# HeadphoneMixer.net
KiCad netlist of a schematic drawn in EAGLE
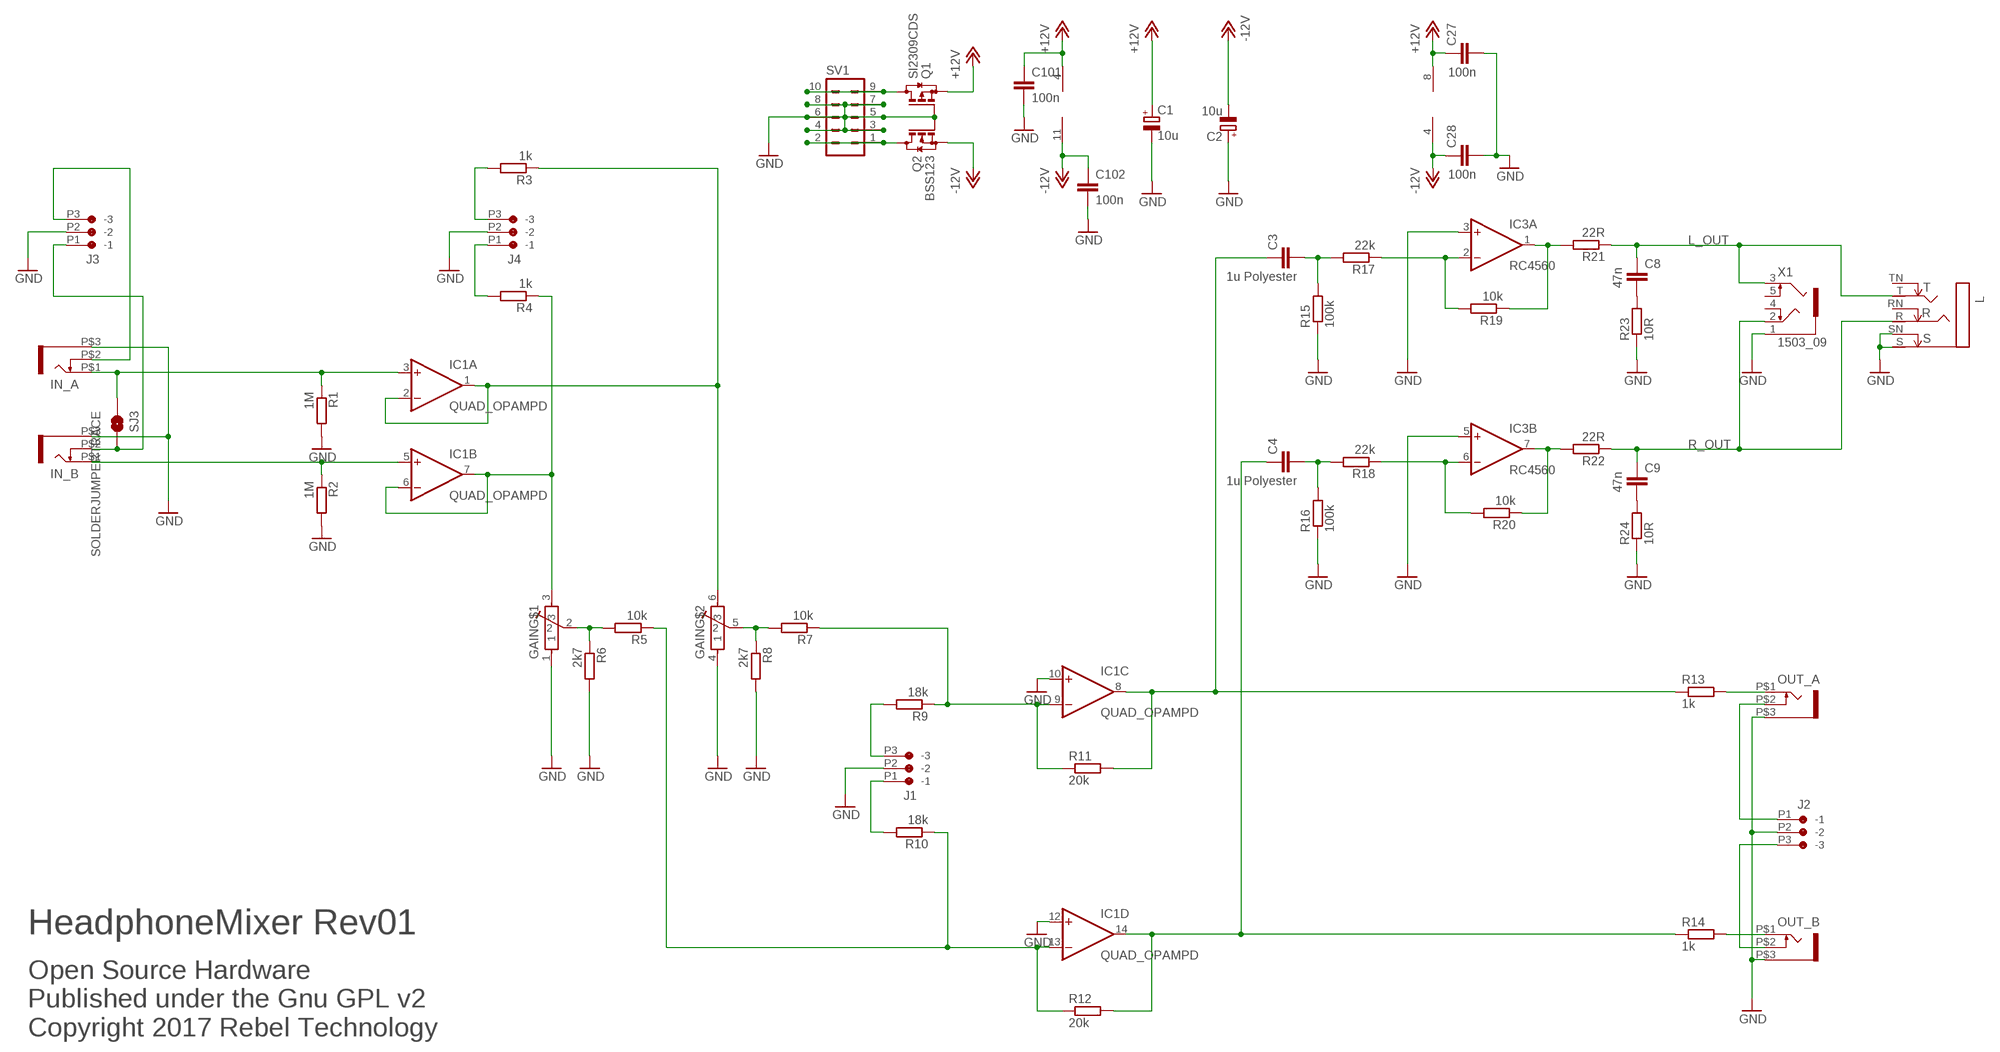
[diagram p0: schematic, sheet 1]

(export (version "E")
  (design (tool "Eeschema 10.0.6"))
  (components
    (comp (ref "C1")
      (value "10u")
      (footprint "eagle-import:153CLV-0505")
      (libsource (lib "eagle-import") (part "CPOL-EU153CLV-0505"))
    )
    (comp (ref "C2")
      (value "10u")
      (footprint "eagle-import:153CLV-0505")
      (libsource (lib "eagle-import") (part "CPOL-EU153CLV-0505"))
    )
    (comp (ref "C3")
      (value "1u Polyester")
      (footprint "eagle-import:C1210")
      (libsource (lib "eagle-import") (part "C-EUC1210"))
    )
    (comp (ref "C4")
      (value "1u Polyester")
      (footprint "eagle-import:C1210")
      (libsource (lib "eagle-import") (part "C-EUC1210"))
    )
    (comp (ref "C8")
      (value "47n")
      (footprint "eagle-import:C0603")
      (libsource (lib "eagle-import") (part "C-EUC0603"))
    )
    (comp (ref "C9")
      (value "47n")
      (footprint "eagle-import:C0603")
      (libsource (lib "eagle-import") (part "C-EUC0603"))
    )
    (comp (ref "C27")
      (value "100n")
      (footprint "eagle-import:C0603")
      (libsource (lib "eagle-import") (part "C-EUC0603"))
    )
    (comp (ref "C28")
      (value "100n")
      (footprint "eagle-import:C0603")
      (libsource (lib "eagle-import") (part "C-EUC0603"))
    )
    (comp (ref "C101")
      (value "100n")
      (footprint "eagle-import:C0603")
      (libsource (lib "eagle-import") (part "C-EUC0603"))
    )
    (comp (ref "C102")
      (value "100n")
      (footprint "eagle-import:C0603")
      (libsource (lib "eagle-import") (part "C-EUC0603"))
    )
    (comp (ref "GAIN")
      (value "POT-BOURNS-PTD902")
      (footprint "eagle-import:POT-BOURNS-PTD902")
      (libsource (lib "eagle-import") (part "POT-BOURNS-PTD902"))
    )
    (comp (ref "IC1")
      (value "QUAD_OPAMPD")
      (footprint "eagle-import:SO14")
      (libsource (lib "eagle-import") (part "QUAD_OPAMPD"))
    )
    (comp (ref "IC3")
      (value "RC4560")
      (footprint "eagle-import:SO08")
      (libsource (lib "eagle-import") (part "NE5532D"))
    )
    (comp (ref "IN_A")
      (value "JACK-UJ-3502-R")
      (footprint "eagle-import:UJ-3502-R")
      (libsource (lib "eagle-import") (part "JACK-UJ-3502-R"))
    )
    (comp (ref "IN_B")
      (value "JACK-UJ-3502-R")
      (footprint "eagle-import:UJ-3502-R")
      (libsource (lib "eagle-import") (part "JACK-UJ-3502-R"))
    )
    (comp (ref "J1")
      (value "CON-JST_PH_3W")
      (footprint "eagle-import:CON-JST_PH_3W")
      (libsource (lib "eagle-import") (part "CON-JST_PH_3W"))
    )
    (comp (ref "J2")
      (value "CON-JST_PH_3W")
      (footprint "eagle-import:CON-JST_PH_3W")
      (libsource (lib "eagle-import") (part "CON-JST_PH_3W"))
    )
    (comp (ref "J3")
      (value "CON-JST_PH_3W")
      (footprint "eagle-import:CON-JST_PH_3W")
      (libsource (lib "eagle-import") (part "CON-JST_PH_3W"))
    )
    (comp (ref "J4")
      (value "CON-JST_PH_3W")
      (footprint "eagle-import:CON-JST_PH_3W")
      (libsource (lib "eagle-import") (part "CON-JST_PH_3W"))
    )
    (comp (ref "L")
      (value "NEUTRIK_NMJ6HCD2")
      (footprint "eagle-import:NMJ6HCD2")
      (libsource (lib "eagle-import") (part "NEUTRIK_NMJ6HCD2"))
    )
    (comp (ref "OUT_A")
      (value "JACK-UJ-3502-R")
      (footprint "eagle-import:UJ-3502-R")
      (libsource (lib "eagle-import") (part "JACK-UJ-3502-R"))
    )
    (comp (ref "OUT_B")
      (value "JACK-UJ-3502-R")
      (footprint "eagle-import:UJ-3502-R")
      (libsource (lib "eagle-import") (part "JACK-UJ-3502-R"))
    )
    (comp (ref "Q1")
      (value "SI2309CDS")
      (footprint "eagle-import:SOT23")
      (libsource (lib "eagle-import") (part "BSS84"))
    )
    (comp (ref "Q2")
      (value "BSS123")
      (footprint "eagle-import:SOT23")
      (libsource (lib "eagle-import") (part "BSS123"))
    )
    (comp (ref "R1")
      (value "1M")
      (footprint "eagle-import:0603")
      (libsource (lib "eagle-import") (part "R-EU_0603"))
    )
    (comp (ref "R2")
      (value "1M")
      (footprint "eagle-import:0603")
      (libsource (lib "eagle-import") (part "R-EU_0603"))
    )
    (comp (ref "R3")
      (value "1k")
      (footprint "eagle-import:0603")
      (libsource (lib "eagle-import") (part "R-EU_0603"))
    )
    (comp (ref "R4")
      (value "1k")
      (footprint "eagle-import:0603")
      (libsource (lib "eagle-import") (part "R-EU_0603"))
    )
    (comp (ref "R5")
      (value "10k")
      (footprint "eagle-import:0603")
      (libsource (lib "eagle-import") (part "R-EU_0603"))
    )
    (comp (ref "R6")
      (value "2k7")
      (footprint "eagle-import:0603")
      (libsource (lib "eagle-import") (part "R-EU_0603"))
    )
    (comp (ref "R7")
      (value "10k")
      (footprint "eagle-import:0603")
      (libsource (lib "eagle-import") (part "R-EU_0603"))
    )
    (comp (ref "R8")
      (value "2k7")
      (footprint "eagle-import:0603")
      (libsource (lib "eagle-import") (part "R-EU_0603"))
    )
    (comp (ref "R9")
      (value "18k")
      (footprint "eagle-import:0603")
      (libsource (lib "eagle-import") (part "R-EU_0603"))
    )
    (comp (ref "R10")
      (value "18k")
      (footprint "eagle-import:0603")
      (libsource (lib "eagle-import") (part "R-EU_0603"))
    )
    (comp (ref "R11")
      (value "20k")
      (footprint "eagle-import:0603")
      (libsource (lib "eagle-import") (part "R-EU_0603"))
    )
    (comp (ref "R12")
      (value "20k")
      (footprint "eagle-import:0603")
      (libsource (lib "eagle-import") (part "R-EU_0603"))
    )
    (comp (ref "R13")
      (value "1k")
      (footprint "eagle-import:0603")
      (libsource (lib "eagle-import") (part "R-EU_0603"))
    )
    (comp (ref "R14")
      (value "1k")
      (footprint "eagle-import:0603")
      (libsource (lib "eagle-import") (part "R-EU_0603"))
    )
    (comp (ref "R15")
      (value "100k")
      (footprint "eagle-import:0603")
      (libsource (lib "eagle-import") (part "R-EU_0603"))
    )
    (comp (ref "R16")
      (value "100k")
      (footprint "eagle-import:0603")
      (libsource (lib "eagle-import") (part "R-EU_0603"))
    )
    (comp (ref "R17")
      (value "22k")
      (footprint "eagle-import:0603")
      (libsource (lib "eagle-import") (part "R-EU_0603"))
    )
    (comp (ref "R18")
      (value "22k")
      (footprint "eagle-import:0603")
      (libsource (lib "eagle-import") (part "R-EU_0603"))
    )
    (comp (ref "R19")
      (value "10k")
      (footprint "eagle-import:0603")
      (libsource (lib "eagle-import") (part "R-EU_0603"))
    )
    (comp (ref "R20")
      (value "10k")
      (footprint "eagle-import:0603")
      (libsource (lib "eagle-import") (part "R-EU_0603"))
    )
    (comp (ref "R21")
      (value "22R")
      (footprint "eagle-import:0603")
      (libsource (lib "eagle-import") (part "R-EU_0603"))
    )
    (comp (ref "R22")
      (value "22R")
      (footprint "eagle-import:0603")
      (libsource (lib "eagle-import") (part "R-EU_0603"))
    )
    (comp (ref "R23")
      (value "10R")
      (footprint "eagle-import:0603")
      (libsource (lib "eagle-import") (part "R-EU_0603"))
    )
    (comp (ref "R24")
      (value "10R")
      (footprint "eagle-import:0603")
      (libsource (lib "eagle-import") (part "R-EU_0603"))
    )
    (comp (ref "SJ3")
      (value "SOLDERJUMPERTRACE")
      (footprint "eagle-import:SJ_2S-TRACE")
      (libsource (lib "eagle-import") (part "SOLDERJUMPERTRACE"))
    )
    (comp (ref "SV1")
      (value "MA05-2")
      (footprint "eagle-import:MA05-2")
      (libsource (lib "eagle-import") (part "MA05-2"))
    )
    (comp (ref "X1")
      (value "1503_09")
      (footprint "eagle-import:1503_09")
      (libsource (lib "eagle-import") (part "1503_09"))
    )
  )
  (nets
    (net (code "1") (name "+12V") (class "Default")
      (node (ref "C1") (pin "+") (pinfunction "+_+") (pintype "passive"))
      (node (ref "C101") (pin "1") (pinfunction "1_1") (pintype "passive"))
      (node (ref "C27") (pin "1") (pinfunction "1_1") (pintype "passive"))
      (node (ref "IC1") (pin "4") (pinfunction "V+_4") (pintype "power_in"))
      (node (ref "IC3") (pin "8") (pinfunction "V+_8") (pintype "power_in"))
      (node (ref "Q1") (pin "2") (pinfunction "S_2") (pintype "passive"))
    )
    (net (code "2") (name "-12V") (class "Default")
      (node (ref "C102") (pin "1") (pinfunction "1_1") (pintype "passive"))
      (node (ref "C2") (pin "-") (pinfunction "-_-") (pintype "passive"))
      (node (ref "C28") (pin "1") (pinfunction "1_1") (pintype "passive"))
      (node (ref "IC1") (pin "11") (pinfunction "V-_11") (pintype "power_in"))
      (node (ref "IC3") (pin "4") (pinfunction "V-_4") (pintype "power_in"))
      (node (ref "Q2") (pin "2") (pinfunction "S_2") (pintype "passive"))
    )
    (net (code "3") (name "/L_OUT") (class "Default")
      (node (ref "C8") (pin "1") (pinfunction "1_1") (pintype "passive"))
      (node (ref "L") (pin "T") (pinfunction "T_T") (pintype "passive"))
      (node (ref "R21") (pin "1") (pinfunction "1_1") (pintype "passive"))
      (node (ref "X1") (pin "3") (pinfunction "3_3") (pintype "passive"))
    )
    (net (code "4") (name "/R_OUT") (class "Default")
      (node (ref "C9") (pin "1") (pinfunction "1_1") (pintype "passive"))
      (node (ref "L") (pin "R") (pinfunction "R_R") (pintype "passive"))
      (node (ref "R22") (pin "1") (pinfunction "1_1") (pintype "passive"))
      (node (ref "X1") (pin "2") (pinfunction "2_2") (pintype "passive"))
    )
    (net (code "5") (name "GND") (class "Default")
      (node (ref "C1") (pin "-") (pinfunction "-_-") (pintype "passive"))
      (node (ref "C101") (pin "2") (pinfunction "2_2") (pintype "passive"))
      (node (ref "C102") (pin "2") (pinfunction "2_2") (pintype "passive"))
      (node (ref "C2") (pin "+") (pinfunction "+_+") (pintype "passive"))
      (node (ref "C27") (pin "2") (pinfunction "2_2") (pintype "passive"))
      (node (ref "C28") (pin "2") (pinfunction "2_2") (pintype "passive"))
      (node (ref "GAIN") (pin "1") (pinfunction "1_1") (pintype "bidirectional"))
      (node (ref "GAIN") (pin "4") (pinfunction "1_4") (pintype "bidirectional"))
      (node (ref "IC1") (pin "10") (pinfunction "+IN_10") (pintype "input"))
      (node (ref "IC1") (pin "12") (pinfunction "+IN_12") (pintype "input"))
      (node (ref "IC3") (pin "3") (pinfunction "+IN_3") (pintype "input"))
      (node (ref "IC3") (pin "5") (pinfunction "+IN_5") (pintype "input"))
      (node (ref "IN_A") (pin "P$3") (pinfunction "SLEEVE_P$3") (pintype "passive"))
      (node (ref "IN_B") (pin "P$3") (pinfunction "SLEEVE_P$3") (pintype "passive"))
      (node (ref "J1") (pin "P2") (pinfunction "-2_P2") (pintype "bidirectional"))
      (node (ref "J2") (pin "P2") (pinfunction "-2_P2") (pintype "bidirectional"))
      (node (ref "J3") (pin "P2") (pinfunction "-2_P2") (pintype "bidirectional"))
      (node (ref "J4") (pin "P2") (pinfunction "-2_P2") (pintype "bidirectional"))
      (node (ref "L") (pin "S") (pinfunction "S_S") (pintype "passive"))
      (node (ref "L") (pin "SN") (pinfunction "SN_SN") (pintype "passive"))
      (node (ref "OUT_A") (pin "P$3") (pinfunction "SLEEVE_P$3") (pintype "passive"))
      (node (ref "OUT_B") (pin "P$3") (pinfunction "SLEEVE_P$3") (pintype "passive"))
      (node (ref "Q1") (pin "1") (pinfunction "G_1") (pintype "passive"))
      (node (ref "Q2") (pin "1") (pinfunction "G_1") (pintype "passive"))
      (node (ref "R1") (pin "2") (pinfunction "2_2") (pintype "passive"))
      (node (ref "R15") (pin "1") (pinfunction "1_1") (pintype "passive"))
      (node (ref "R16") (pin "1") (pinfunction "1_1") (pintype "passive"))
      (node (ref "R2") (pin "2") (pinfunction "2_2") (pintype "passive"))
      (node (ref "R23") (pin "1") (pinfunction "1_1") (pintype "passive"))
      (node (ref "R24") (pin "1") (pinfunction "1_1") (pintype "passive"))
      (node (ref "R6") (pin "2") (pinfunction "2_2") (pintype "passive"))
      (node (ref "R8") (pin "2") (pinfunction "2_2") (pintype "passive"))
      (node (ref "SV1") (pin "3") (pinfunction "3_3") (pintype "passive"))
      (node (ref "SV1") (pin "4") (pinfunction "4_4") (pintype "passive"))
      (node (ref "SV1") (pin "5") (pinfunction "5_5") (pintype "passive"))
      (node (ref "SV1") (pin "6") (pinfunction "6_6") (pintype "passive"))
      (node (ref "SV1") (pin "7") (pinfunction "7_7") (pintype "passive"))
      (node (ref "SV1") (pin "8") (pinfunction "8_8") (pintype "passive"))
      (node (ref "X1") (pin "1") (pinfunction "1_1") (pintype "passive"))
    )
    (net (code "6") (name "Net-(C3-Pad2)") (class "Default")
      (node (ref "C3") (pin "2") (pinfunction "2_2") (pintype "passive"))
      (node (ref "R15") (pin "2") (pinfunction "2_2") (pintype "passive"))
      (node (ref "R17") (pin "2") (pinfunction "2_2") (pintype "passive"))
    )
    (net (code "7") (name "Net-(C4-Pad2)") (class "Default")
      (node (ref "C4") (pin "2") (pinfunction "2_2") (pintype "passive"))
      (node (ref "R16") (pin "2") (pinfunction "2_2") (pintype "passive"))
      (node (ref "R18") (pin "2") (pinfunction "2_2") (pintype "passive"))
    )
    (net (code "8") (name "Net-(C8-Pad2)") (class "Default")
      (node (ref "C8") (pin "2") (pinfunction "2_2") (pintype "passive"))
      (node (ref "R23") (pin "2") (pinfunction "2_2") (pintype "passive"))
    )
    (net (code "9") (name "Net-(C9-Pad2)") (class "Default")
      (node (ref "C9") (pin "2") (pinfunction "2_2") (pintype "passive"))
      (node (ref "R24") (pin "2") (pinfunction "2_2") (pintype "passive"))
    )
    (net (code "10") (name "Net-(GAIN-Pad2)") (class "Default")
      (node (ref "GAIN") (pin "2") (pinfunction "2_2") (pintype "bidirectional"))
      (node (ref "R5") (pin "2") (pinfunction "2_2") (pintype "passive"))
      (node (ref "R6") (pin "1") (pinfunction "1_1") (pintype "passive"))
    )
    (net (code "11") (name "Net-(GAINB-2)") (class "Default")
      (node (ref "GAIN") (pin "5") (pinfunction "2_5") (pintype "bidirectional"))
      (node (ref "R7") (pin "2") (pinfunction "2_2") (pintype "passive"))
      (node (ref "R8") (pin "1") (pinfunction "1_1") (pintype "passive"))
    )
    (net (code "12") (name "Net-(GAINB-3)") (class "Default")
      (node (ref "GAIN") (pin "6") (pinfunction "3_6") (pintype "bidirectional"))
      (node (ref "IC1") (pin "1") (pinfunction "OUT_1") (pintype "output"))
      (node (ref "IC1") (pin "2") (pinfunction "-IN_2") (pintype "input"))
      (node (ref "R3") (pin "1") (pinfunction "1_1") (pintype "passive"))
    )
    (net (code "13") (name "Net-(IC1A-+IN)") (class "Default")
      (node (ref "IC1") (pin "3") (pinfunction "+IN_3") (pintype "input"))
      (node (ref "IN_A") (pin "P$1") (pinfunction "TIP_P$1") (pintype "passive"))
      (node (ref "R1") (pin "1") (pinfunction "1_1") (pintype "passive"))
      (node (ref "SJ3") (pin "1") (pinfunction "1_1") (pintype "passive"))
    )
    (net (code "14") (name "Net-(IC1B-+IN)") (class "Default")
      (node (ref "IC1") (pin "5") (pinfunction "+IN_5") (pintype "input"))
      (node (ref "IN_B") (pin "P$1") (pinfunction "TIP_P$1") (pintype "passive"))
      (node (ref "R2") (pin "1") (pinfunction "1_1") (pintype "passive"))
    )
    (net (code "15") (name "Net-(IC1B--IN)") (class "Default")
      (node (ref "GAIN") (pin "3") (pinfunction "3_3") (pintype "bidirectional"))
      (node (ref "IC1") (pin "6") (pinfunction "-IN_6") (pintype "input"))
      (node (ref "IC1") (pin "7") (pinfunction "OUT_7") (pintype "output"))
      (node (ref "R4") (pin "1") (pinfunction "1_1") (pintype "passive"))
    )
    (net (code "16") (name "Net-(IC1C--IN)") (class "Default")
      (node (ref "IC1") (pin "9") (pinfunction "-IN_9") (pintype "input"))
      (node (ref "R11") (pin "1") (pinfunction "1_1") (pintype "passive"))
      (node (ref "R7") (pin "1") (pinfunction "1_1") (pintype "passive"))
      (node (ref "R9") (pin "1") (pinfunction "1_1") (pintype "passive"))
    )
    (net (code "17") (name "Net-(IC1C-OUT)") (class "Default")
      (node (ref "C3") (pin "1") (pinfunction "1_1") (pintype "passive"))
      (node (ref "IC1") (pin "8") (pinfunction "OUT_8") (pintype "output"))
      (node (ref "R11") (pin "2") (pinfunction "2_2") (pintype "passive"))
      (node (ref "R13") (pin "1") (pinfunction "1_1") (pintype "passive"))
    )
    (net (code "18") (name "Net-(IC1D--IN)") (class "Default")
      (node (ref "IC1") (pin "13") (pinfunction "-IN_13") (pintype "input"))
      (node (ref "R10") (pin "1") (pinfunction "1_1") (pintype "passive"))
      (node (ref "R12") (pin "1") (pinfunction "1_1") (pintype "passive"))
      (node (ref "R5") (pin "1") (pinfunction "1_1") (pintype "passive"))
    )
    (net (code "19") (name "Net-(IC1D-OUT)") (class "Default")
      (node (ref "C4") (pin "1") (pinfunction "1_1") (pintype "passive"))
      (node (ref "IC1") (pin "14") (pinfunction "OUT_14") (pintype "output"))
      (node (ref "R12") (pin "2") (pinfunction "2_2") (pintype "passive"))
      (node (ref "R14") (pin "1") (pinfunction "1_1") (pintype "passive"))
    )
    (net (code "20") (name "Net-(IC3A--IN)") (class "Default")
      (node (ref "IC3") (pin "2") (pinfunction "-IN_2") (pintype "input"))
      (node (ref "R17") (pin "1") (pinfunction "1_1") (pintype "passive"))
      (node (ref "R19") (pin "2") (pinfunction "2_2") (pintype "passive"))
    )
    (net (code "21") (name "Net-(IC3A-OUT)") (class "Default")
      (node (ref "IC3") (pin "1") (pinfunction "OUT_1") (pintype "output"))
      (node (ref "R19") (pin "1") (pinfunction "1_1") (pintype "passive"))
      (node (ref "R21") (pin "2") (pinfunction "2_2") (pintype "passive"))
    )
    (net (code "22") (name "Net-(IC3B--IN)") (class "Default")
      (node (ref "IC3") (pin "6") (pinfunction "-IN_6") (pintype "input"))
      (node (ref "R18") (pin "1") (pinfunction "1_1") (pintype "passive"))
      (node (ref "R20") (pin "2") (pinfunction "2_2") (pintype "passive"))
    )
    (net (code "23") (name "Net-(IC3B-OUT)") (class "Default")
      (node (ref "IC3") (pin "7") (pinfunction "OUT_7") (pintype "output"))
      (node (ref "R20") (pin "1") (pinfunction "1_1") (pintype "passive"))
      (node (ref "R22") (pin "2") (pinfunction "2_2") (pintype "passive"))
    )
    (net (code "24") (name "Net-(IN_A-SW)") (class "Default")
      (node (ref "IN_A") (pin "P$2") (pinfunction "SW_P$2") (pintype "passive"))
      (node (ref "J3") (pin "P3") (pinfunction "-3_P3") (pintype "bidirectional"))
    )
    (net (code "25") (name "Net-(IN_B-SW)") (class "Default")
      (node (ref "IN_B") (pin "P$2") (pinfunction "SW_P$2") (pintype "passive"))
      (node (ref "J3") (pin "P1") (pinfunction "-1_P1") (pintype "bidirectional"))
      (node (ref "SJ3") (pin "2") (pinfunction "2_2") (pintype "passive"))
    )
    (net (code "26") (name "Net-(J1--1)") (class "Default")
      (node (ref "J1") (pin "P1") (pinfunction "-1_P1") (pintype "bidirectional"))
      (node (ref "R10") (pin "2") (pinfunction "2_2") (pintype "passive"))
    )
    (net (code "27") (name "Net-(J1--3)") (class "Default")
      (node (ref "J1") (pin "P3") (pinfunction "-3_P3") (pintype "bidirectional"))
      (node (ref "R9") (pin "2") (pinfunction "2_2") (pintype "passive"))
    )
    (net (code "28") (name "Net-(J2--1)") (class "Default")
      (node (ref "J2") (pin "P1") (pinfunction "-1_P1") (pintype "bidirectional"))
      (node (ref "OUT_A") (pin "P$2") (pinfunction "SW_P$2") (pintype "passive"))
    )
    (net (code "29") (name "Net-(J2--3)") (class "Default")
      (node (ref "J2") (pin "P3") (pinfunction "-3_P3") (pintype "bidirectional"))
      (node (ref "OUT_B") (pin "P$2") (pinfunction "SW_P$2") (pintype "passive"))
    )
    (net (code "30") (name "Net-(J4--1)") (class "Default")
      (node (ref "J4") (pin "P1") (pinfunction "-1_P1") (pintype "bidirectional"))
      (node (ref "R4") (pin "2") (pinfunction "2_2") (pintype "passive"))
    )
    (net (code "31") (name "Net-(J4--3)") (class "Default")
      (node (ref "J4") (pin "P3") (pinfunction "-3_P3") (pintype "bidirectional"))
      (node (ref "R3") (pin "2") (pinfunction "2_2") (pintype "passive"))
    )
    (net (code "32") (name "Net-(OUT_A-TIP)") (class "Default")
      (node (ref "OUT_A") (pin "P$1") (pinfunction "TIP_P$1") (pintype "passive"))
      (node (ref "R13") (pin "2") (pinfunction "2_2") (pintype "passive"))
    )
    (net (code "33") (name "Net-(OUT_B-TIP)") (class "Default")
      (node (ref "OUT_B") (pin "P$1") (pinfunction "TIP_P$1") (pintype "passive"))
      (node (ref "R14") (pin "2") (pinfunction "2_2") (pintype "passive"))
    )
    (net (code "34") (name "Net-(Q1-D)") (class "Default")
      (node (ref "Q1") (pin "3") (pinfunction "D_3") (pintype "passive"))
      (node (ref "SV1") (pin "10") (pinfunction "10_10") (pintype "passive"))
      (node (ref "SV1") (pin "9") (pinfunction "9_9") (pintype "passive"))
    )
    (net (code "35") (name "Net-(Q2-D)") (class "Default")
      (node (ref "Q2") (pin "3") (pinfunction "D_3") (pintype "passive"))
      (node (ref "SV1") (pin "1") (pinfunction "1_1") (pintype "passive"))
      (node (ref "SV1") (pin "2") (pinfunction "2_2") (pintype "passive"))
    )
    (net (code "36") (name "unconnected-(L-PadRN)") (class "Default")
      (node (ref "L") (pin "RN") (pinfunction "RN_RN") (pintype "passive"))
    )
    (net (code "37") (name "unconnected-(L-PadTN)") (class "Default")
      (node (ref "L") (pin "TN") (pinfunction "TN_TN") (pintype "passive"))
    )
    (net (code "38") (name "unconnected-(X1-Pad4)") (class "Default")
      (node (ref "X1") (pin "4") (pinfunction "4_4") (pintype "passive"))
    )
    (net (code "39") (name "unconnected-(X1-Pad5)") (class "Default")
      (node (ref "X1") (pin "5") (pinfunction "5_5") (pintype "passive"))
    )
  )
)
